# Bubbler.net
KiCad netlist of a schematic drawn in EAGLE
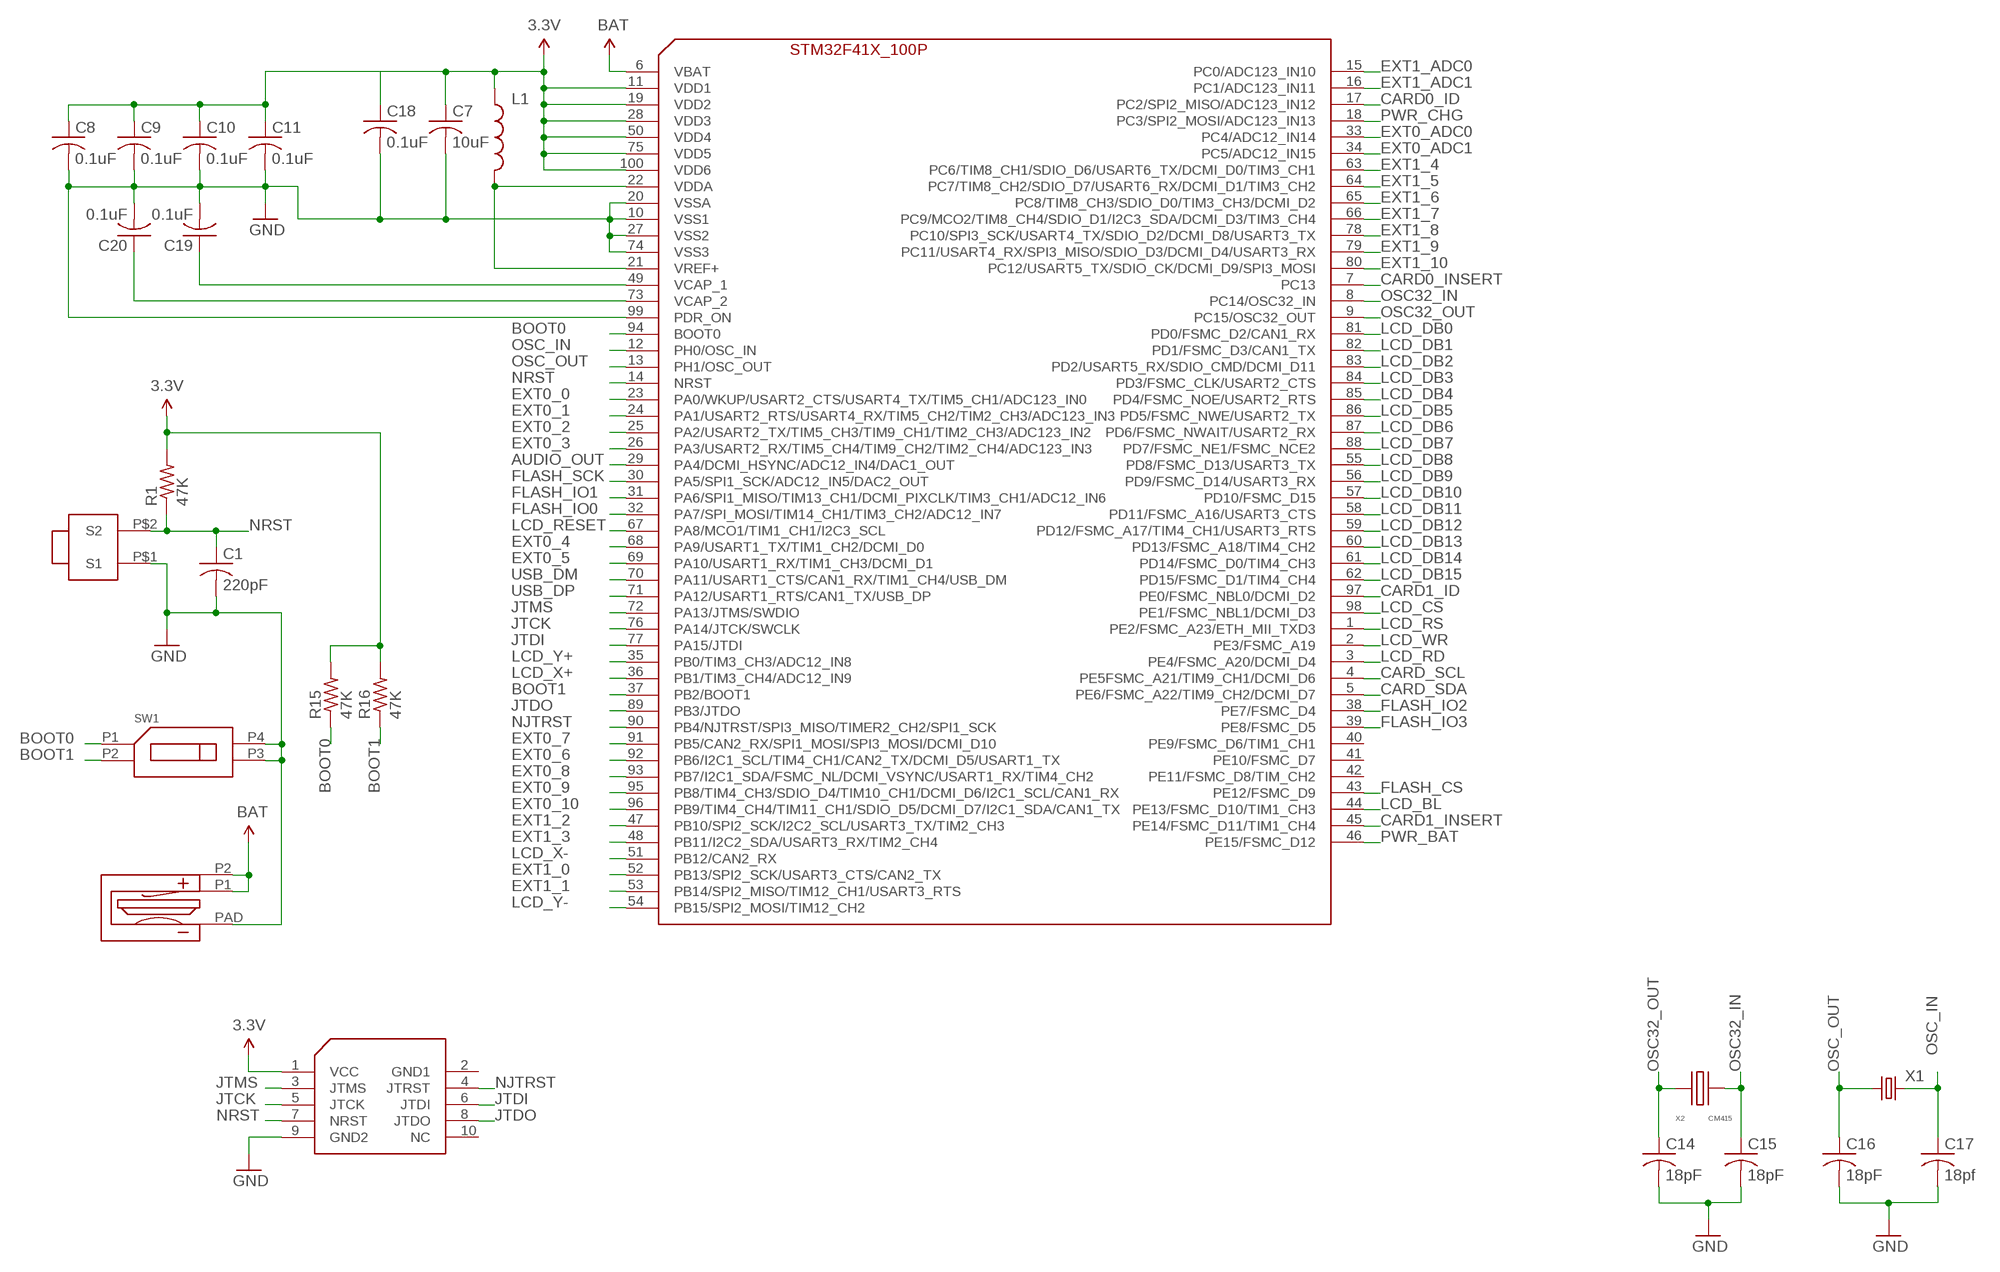
[diagram p0: schematic, sheet 1]
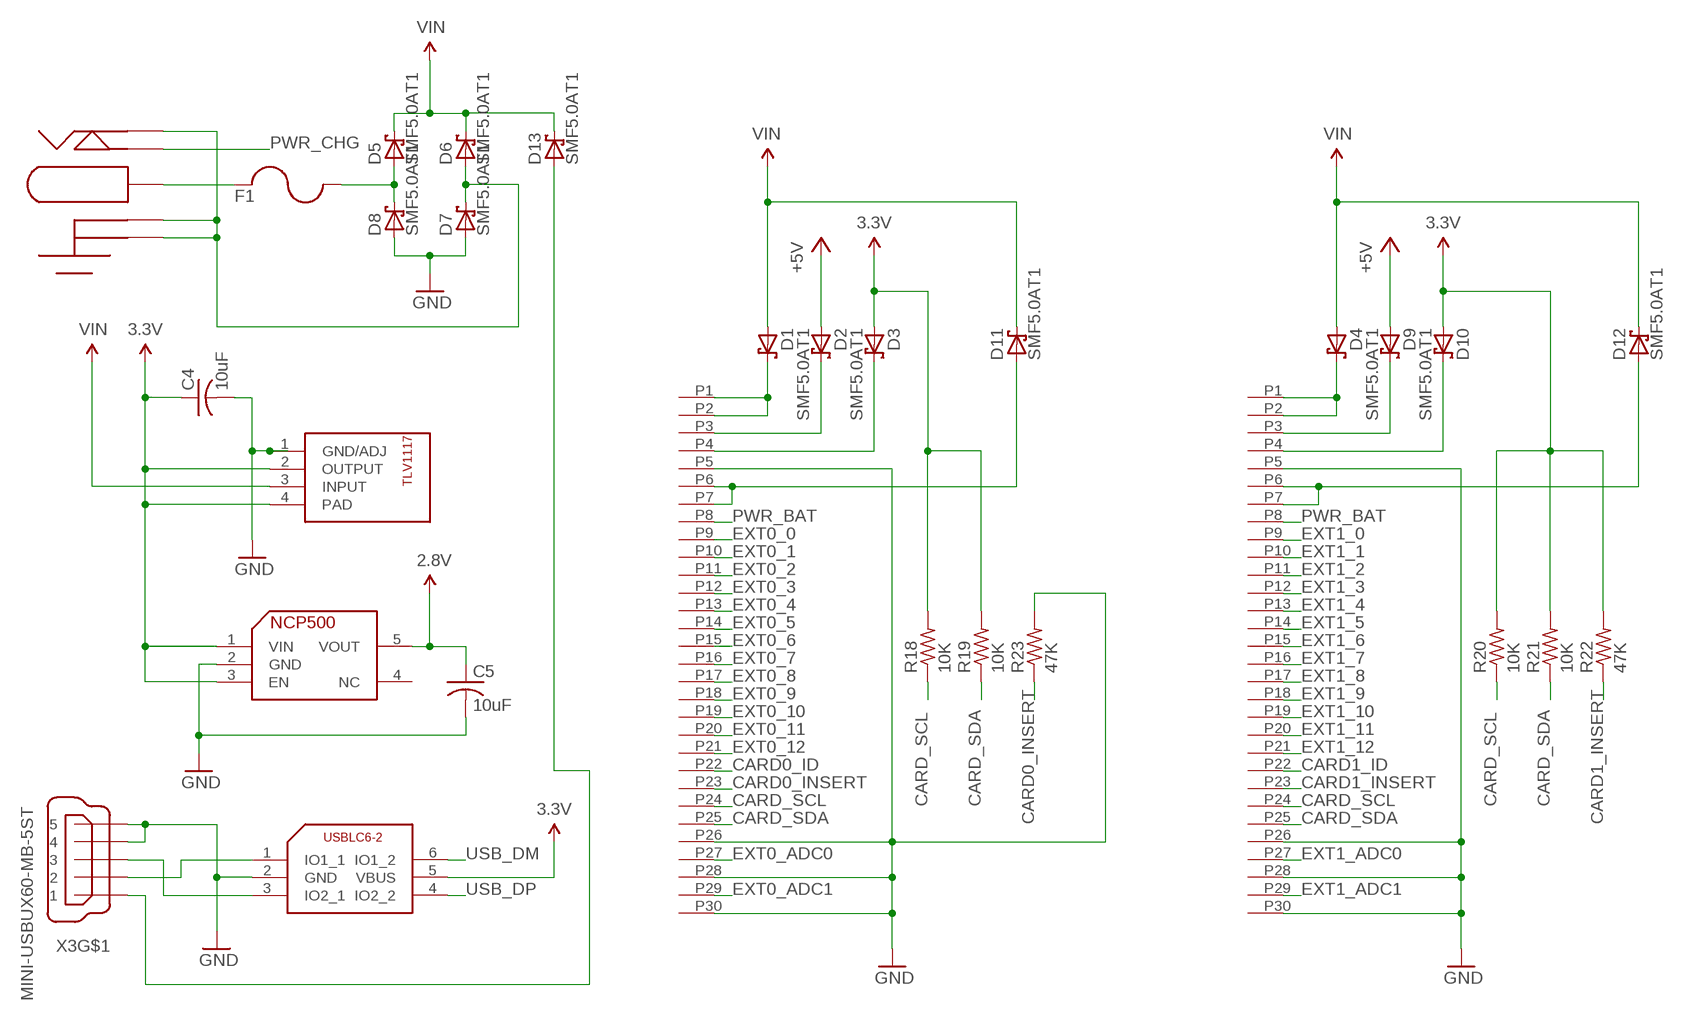
[diagram p1: schematic, sheet 2]
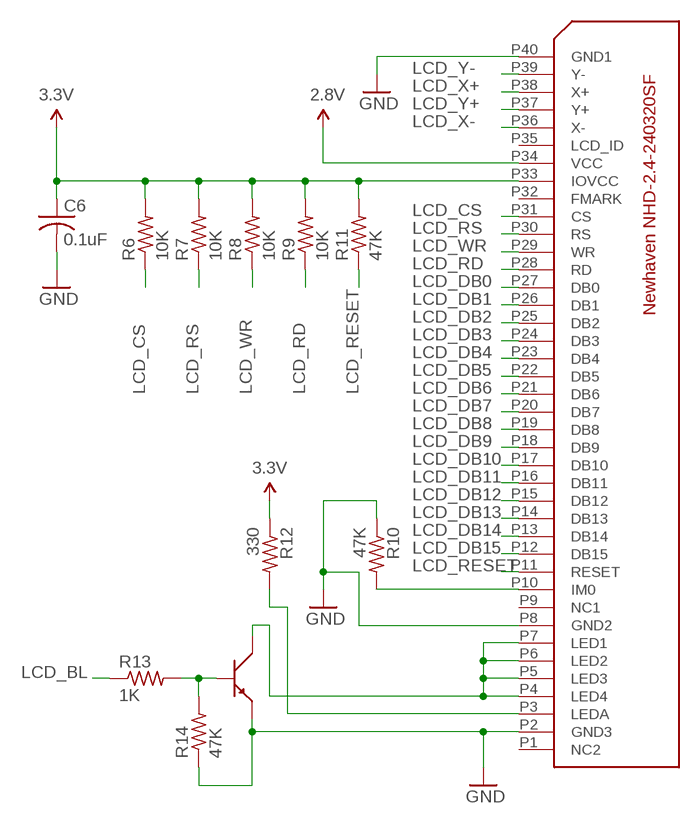
[diagram p2: schematic, sheet 3]
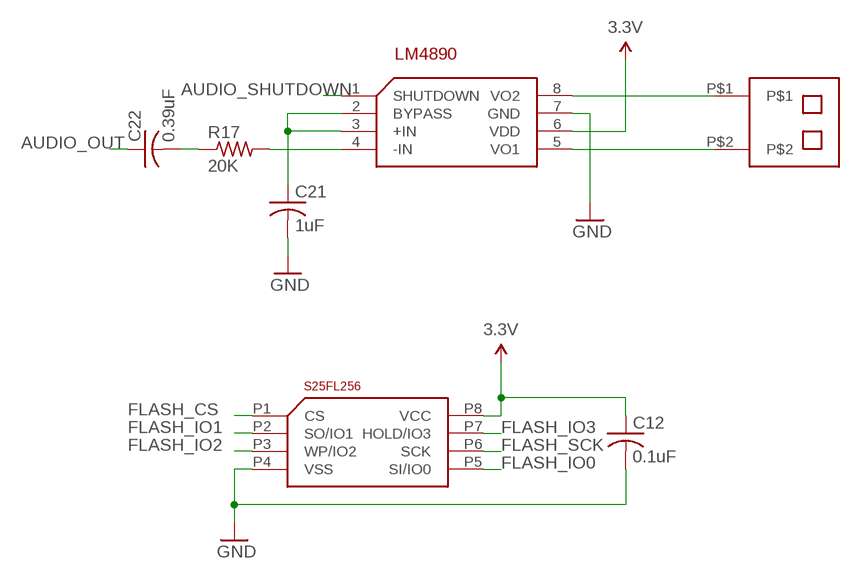
[diagram p3: schematic, sheet 4]

(export (version "E")
  (design (tool "Eeschema 10.0.6"))
  (components
    (comp (ref "B1")
      (value "BATTERY-LINX-HLD-001")
      (footprint "eagle-import:BATTERY-LINX-HLD-001")
      (libsource (lib "eagle-import") (part "BATTERY-LINX-HLD-001"))
    )
    (comp (ref "C1")
      (value "220pF")
      (footprint "eagle-import:C0402")
      (libsource (lib "eagle-import") (part "C-USC0402"))
    )
    (comp (ref "C7")
      (value "10uF")
      (footprint "eagle-import:C0805")
      (libsource (lib "eagle-import") (part "C-USC0805"))
    )
    (comp (ref "C8")
      (value "0.1uF")
      (footprint "eagle-import:C0402")
      (libsource (lib "eagle-import") (part "C-USC0402"))
    )
    (comp (ref "C9")
      (value "0.1uF")
      (footprint "eagle-import:C0402")
      (libsource (lib "eagle-import") (part "C-USC0402"))
    )
    (comp (ref "C10")
      (value "0.1uF")
      (footprint "eagle-import:C0402")
      (libsource (lib "eagle-import") (part "C-USC0402"))
    )
    (comp (ref "C11")
      (value "0.1uF")
      (footprint "eagle-import:C0402")
      (libsource (lib "eagle-import") (part "C-USC0402"))
    )
    (comp (ref "C14")
      (value "18pF")
      (footprint "eagle-import:C0402")
      (libsource (lib "eagle-import") (part "C-USC0402"))
    )
    (comp (ref "C15")
      (value "18pF")
      (footprint "eagle-import:C0402")
      (libsource (lib "eagle-import") (part "C-USC0402"))
    )
    (comp (ref "C16")
      (value "18pF")
      (footprint "eagle-import:C0402")
      (libsource (lib "eagle-import") (part "C-USC0402"))
    )
    (comp (ref "C17")
      (value "18pf")
      (footprint "eagle-import:C0402")
      (libsource (lib "eagle-import") (part "C-USC0402"))
    )
    (comp (ref "C18")
      (value "0.1uF")
      (footprint "eagle-import:C0402")
      (libsource (lib "eagle-import") (part "C-USC0402"))
    )
    (comp (ref "C19")
      (value "0.1uF")
      (footprint "eagle-import:C0402")
      (libsource (lib "eagle-import") (part "C-USC0402"))
    )
    (comp (ref "C20")
      (value "0.1uF")
      (footprint "eagle-import:C0402")
      (libsource (lib "eagle-import") (part "C-USC0402"))
    )
    (comp (ref "L1")
      (value "INDUCTOR0603")
      (footprint "eagle-import:0603")
      (libsource (lib "eagle-import") (part "INDUCTOR0603"))
    )
    (comp (ref "R1")
      (value "47K")
      (footprint "eagle-import:R0402")
      (libsource (lib "eagle-import") (part "R-US_R0402"))
    )
    (comp (ref "R15")
      (value "47K")
      (footprint "eagle-import:R0402")
      (libsource (lib "eagle-import") (part "R-US_R0402"))
    )
    (comp (ref "R16")
      (value "47K")
      (footprint "eagle-import:R0402")
      (libsource (lib "eagle-import") (part "R-US_R0402"))
    )
    (comp (ref "SW1")
      (value "SWITCH-DIP-GDH-02")
      (footprint "eagle-import:SWITCH-DIP-GDH-02")
      (libsource (lib "eagle-import") (part "SWITCH-DIP-GDH-02"))
    )
    (comp (ref "SW2")
      (value "ITT-SWITCH-KSS-G")
      (footprint "eagle-import:ITT-KSS-G")
      (libsource (lib "eagle-import") (part "ITT-SWITCH-KSS-G"))
    )
    (comp (ref "U$1")
      (value "STM32-JTAG-10P")
      (footprint "eagle-import:STM32-JTAG-10P")
      (libsource (lib "eagle-import") (part "STM32-JTAG-10P"))
    )
    (comp (ref "U1")
      (value "STM32F41X-100P")
      (footprint "eagle-import:TQFP100")
      (libsource (lib "eagle-import") (part "STM32F41X-100P"))
    )
    (comp (ref "X1")
      (value "CRYSTAL5X3")
      (footprint "eagle-import:CRYSTAL-SMD-5X3")
      (libsource (lib "eagle-import") (part "CRYSTAL5X3"))
    )
    (comp (ref "X2")
      (value "CM415")
      (footprint "eagle-import:CM415")
      (libsource (lib "eagle-import") (part "CM415"))
    )
    (comp (ref "C12")
      (value "0.1uF")
      (footprint "eagle-import:C0402")
      (libsource (lib "eagle-import") (part "C-USC0402"))
    )
    (comp (ref "C21")
      (value "1uF")
      (footprint "eagle-import:C0402")
      (libsource (lib "eagle-import") (part "C-USC0402"))
    )
    (comp (ref "C22")
      (value "0.39uF")
      (footprint "eagle-import:C0402")
      (libsource (lib "eagle-import") (part "C-USC0402"))
    )
    (comp (ref "R17")
      (value "20K")
      (footprint "eagle-import:R0402")
      (libsource (lib "eagle-import") (part "R-US_R0402"))
    )
    (comp (ref "U2")
      (value "SPANSION-S25FL256")
      (footprint "eagle-import:SPANSION-WSON-8")
      (libsource (lib "eagle-import") (part "SPANSION-S25FL256"))
    )
    (comp (ref "U3")
      (value "LM4890")
      (footprint "eagle-import:TSSOP8")
      (libsource (lib "eagle-import") (part "LM4890"))
    )
    (comp (ref "U7")
      (value "MOLEX-1.25-WTB-RA-CONN-2POS")
      (footprint "eagle-import:MOLEX-1.25WTB-RA-CONN")
      (libsource (lib "eagle-import") (part "MOLEX-1.25-WTB-RA-CONN-2POS"))
    )
    (comp (ref "C4")
      (value "10uF")
      (footprint "eagle-import:C1206")
      (libsource (lib "eagle-import") (part "C-USC1206"))
    )
    (comp (ref "C5")
      (value "10uF")
      (footprint "eagle-import:C1206")
      (libsource (lib "eagle-import") (part "C-USC1206"))
    )
    (comp (ref "CARD0")
      (value "CONNECTOR-JAE-TX24-30F")
      (footprint "eagle-import:CONNECTOR-JAE-TX24-30")
      (libsource (lib "eagle-import") (part "CONNECTOR-JAE-TX24-30F"))
    )
    (comp (ref "CARD1")
      (value "CONNECTOR-JAE-TX24-30F")
      (footprint "eagle-import:CONNECTOR-JAE-TX24-30")
      (libsource (lib "eagle-import") (part "CONNECTOR-JAE-TX24-30F"))
    )
    (comp (ref "D1")
      (value "SCHOTTKY-DIODESMD")
      (footprint "eagle-import:SMB")
      (libsource (lib "eagle-import") (part "SCHOTTKY-DIODESMD"))
    )
    (comp (ref "D2")
      (value "SMF5.0AT1")
      (footprint "eagle-import:SOD123FL")
      (libsource (lib "eagle-import") (part "SMF5.0AT1"))
    )
    (comp (ref "D3")
      (value "SMF5.0AT1")
      (footprint "eagle-import:SOD123FL")
      (libsource (lib "eagle-import") (part "SMF5.0AT1"))
    )
    (comp (ref "D4")
      (value "SCHOTTKY-DIODESMD")
      (footprint "eagle-import:SMB")
      (libsource (lib "eagle-import") (part "SCHOTTKY-DIODESMD"))
    )
    (comp (ref "D5")
      (value "SMF5.0AT1")
      (footprint "eagle-import:SOD123FL")
      (libsource (lib "eagle-import") (part "SMF5.0AT1"))
    )
    (comp (ref "D6")
      (value "SMF5.0AT1")
      (footprint "eagle-import:SOD123FL")
      (libsource (lib "eagle-import") (part "SMF5.0AT1"))
    )
    (comp (ref "D7")
      (value "SMF5.0AT1")
      (footprint "eagle-import:SOD123FL")
      (libsource (lib "eagle-import") (part "SMF5.0AT1"))
    )
    (comp (ref "D8")
      (value "SMF5.0AT1")
      (footprint "eagle-import:SOD123FL")
      (libsource (lib "eagle-import") (part "SMF5.0AT1"))
    )
    (comp (ref "D9")
      (value "SMF5.0AT1")
      (footprint "eagle-import:SOD123FL")
      (libsource (lib "eagle-import") (part "SMF5.0AT1"))
    )
    (comp (ref "D10")
      (value "SMF5.0AT1")
      (footprint "eagle-import:SOD123FL")
      (libsource (lib "eagle-import") (part "SMF5.0AT1"))
    )
    (comp (ref "D11")
      (value "SMF5.0AT1")
      (footprint "eagle-import:SOD123FL")
      (libsource (lib "eagle-import") (part "SMF5.0AT1"))
    )
    (comp (ref "D12")
      (value "SMF5.0AT1")
      (footprint "eagle-import:SOD123FL")
      (libsource (lib "eagle-import") (part "SMF5.0AT1"))
    )
    (comp (ref "D13")
      (value "SMF5.0AT1")
      (footprint "eagle-import:SOD123FL")
      (libsource (lib "eagle-import") (part "SMF5.0AT1"))
    )
    (comp (ref "F1")
      (value "BOURNES-PTC-MF-SMXXXMF-SM030")
      (footprint "eagle-import:MF-SM030")
      (libsource (lib "eagle-import") (part "BOURNES-PTC-MF-SMXXXMF-SM030"))
    )
    (comp (ref "R18")
      (value "10K")
      (footprint "eagle-import:R0402")
      (libsource (lib "eagle-import") (part "R-US_R0402"))
    )
    (comp (ref "R19")
      (value "10K")
      (footprint "eagle-import:R0402")
      (libsource (lib "eagle-import") (part "R-US_R0402"))
    )
    (comp (ref "R20")
      (value "10K")
      (footprint "eagle-import:R0402")
      (libsource (lib "eagle-import") (part "R-US_R0402"))
    )
    (comp (ref "R21")
      (value "10K")
      (footprint "eagle-import:R0402")
      (libsource (lib "eagle-import") (part "R-US_R0402"))
    )
    (comp (ref "R22")
      (value "47K")
      (footprint "eagle-import:R0402")
      (libsource (lib "eagle-import") (part "R-US_R0402"))
    )
    (comp (ref "R23")
      (value "47K")
      (footprint "eagle-import:R0402")
      (libsource (lib "eagle-import") (part "R-US_R0402"))
    )
    (comp (ref "U$2")
      (value "DCJACK-CUI-PJ051AH")
      (footprint "eagle-import:DCJACK_CUI_PJ012B")
      (libsource (lib "eagle-import") (part "DCJACK-CUI-PJ051AH"))
    )
    (comp (ref "U$7")
      (value "NCP500")
      (footprint "eagle-import:SOT23-5L")
      (libsource (lib "eagle-import") (part "NCP500"))
    )
    (comp (ref "U5")
      (value "USBLC6-2")
      (footprint "eagle-import:SOT23-6L")
      (libsource (lib "eagle-import") (part "USBLC6-2"))
    )
    (comp (ref "U6")
      (value "TLV1117")
      (footprint "eagle-import:SOT223")
      (libsource (lib "eagle-import") (part "TLV1117"))
    )
    (comp (ref "X3")
      (value "MINI-USBUX60-MB-5ST")
      (footprint "eagle-import:DUBLIB_UX60-MB-5ST")
      (libsource (lib "eagle-import") (part "MINI-USBUX60-MB-5ST"))
    )
    (comp (ref "C6")
      (value "0.1uF")
      (footprint "eagle-import:C0402")
      (libsource (lib "eagle-import") (part "C-USC0402"))
    )
    (comp (ref "R6")
      (value "10K")
      (footprint "eagle-import:R0402")
      (libsource (lib "eagle-import") (part "R-US_R0402"))
    )
    (comp (ref "R7")
      (value "10K")
      (footprint "eagle-import:R0402")
      (libsource (lib "eagle-import") (part "R-US_R0402"))
    )
    (comp (ref "R8")
      (value "10K")
      (footprint "eagle-import:R0402")
      (libsource (lib "eagle-import") (part "R-US_R0402"))
    )
    (comp (ref "R9")
      (value "10K")
      (footprint "eagle-import:R0402")
      (libsource (lib "eagle-import") (part "R-US_R0402"))
    )
    (comp (ref "R10")
      (value "47K")
      (footprint "eagle-import:R0402")
      (libsource (lib "eagle-import") (part "R-US_R0402"))
    )
    (comp (ref "R11")
      (value "47K")
      (footprint "eagle-import:R0402")
      (libsource (lib "eagle-import") (part "R-US_R0402"))
    )
    (comp (ref "R12")
      (value "330")
      (footprint "eagle-import:R1206")
      (libsource (lib "eagle-import") (part "R-US_R1206"))
    )
    (comp (ref "R13")
      (value "1K")
      (footprint "eagle-import:R0402")
      (libsource (lib "eagle-import") (part "R-US_R0402"))
    )
    (comp (ref "R14")
      (value "47K")
      (footprint "eagle-import:R0402")
      (libsource (lib "eagle-import") (part "R-US_R0402"))
    )
    (comp (ref "U$10")
      (value "NHD-2.4-240320SF")
      (footprint "eagle-import:MOLEX-534132-060")
      (libsource (lib "eagle-import") (part "NHD-2.4-240320SF"))
    )
    (comp (ref "U4")
      (value "BIPOLAR-PMBT6428")
      (footprint "eagle-import:DUBLIB_SOT23")
      (libsource (lib "eagle-import") (part "BIPOLAR-PMBT6428"))
    )
  )
  (nets
    (net (code "1") (name "+5V") (class "Default")
      (node (ref "D2") (pin "A") (pinfunction "A_A") (pintype "passive"))
      (node (ref "D9") (pin "A") (pinfunction "A_A") (pintype "passive"))
    )
    (net (code "2") (name "2.8V") (class "Default")
      (node (ref "C5") (pin "1") (pinfunction "1_1") (pintype "passive"))
      (node (ref "U$10") (pin "P34") (pinfunction "VCC_P34") (pintype "bidirectional"))
      (node (ref "U$7") (pin "5") (pinfunction "VOUT_5") (pintype "bidirectional"))
    )
    (net (code "3") (name "3.3V") (class "Default")
      (node (ref "C10") (pin "1") (pinfunction "1_1") (pintype "passive"))
      (node (ref "C11") (pin "1") (pinfunction "1_1") (pintype "passive"))
      (node (ref "C12") (pin "1") (pinfunction "1_1") (pintype "passive"))
      (node (ref "C18") (pin "1") (pinfunction "1_1") (pintype "passive"))
      (node (ref "C4") (pin "1") (pinfunction "1_1") (pintype "passive"))
      (node (ref "C6") (pin "1") (pinfunction "1_1") (pintype "passive"))
      (node (ref "C7") (pin "1") (pinfunction "1_1") (pintype "passive"))
      (node (ref "C8") (pin "1") (pinfunction "1_1") (pintype "passive"))
      (node (ref "C9") (pin "1") (pinfunction "1_1") (pintype "passive"))
      (node (ref "D10") (pin "A") (pinfunction "A_A") (pintype "passive"))
      (node (ref "D3") (pin "A") (pinfunction "A_A") (pintype "passive"))
      (node (ref "L1") (pin "1") (pinfunction "1_1") (pintype "passive"))
      (node (ref "R1") (pin "2") (pinfunction "2_2") (pintype "passive"))
      (node (ref "R11") (pin "2") (pinfunction "2_2") (pintype "passive"))
      (node (ref "R12") (pin "1") (pinfunction "1_1") (pintype "passive"))
      (node (ref "R15") (pin "2") (pinfunction "2_2") (pintype "passive"))
      (node (ref "R16") (pin "2") (pinfunction "2_2") (pintype "passive"))
      (node (ref "R18") (pin "2") (pinfunction "2_2") (pintype "passive"))
      (node (ref "R19") (pin "2") (pinfunction "2_2") (pintype "passive"))
      (node (ref "R20") (pin "2") (pinfunction "2_2") (pintype "passive"))
      (node (ref "R21") (pin "2") (pinfunction "2_2") (pintype "passive"))
      (node (ref "R22") (pin "2") (pinfunction "2_2") (pintype "passive"))
      (node (ref "R6") (pin "2") (pinfunction "2_2") (pintype "passive"))
      (node (ref "R7") (pin "2") (pinfunction "2_2") (pintype "passive"))
      (node (ref "R8") (pin "2") (pinfunction "2_2") (pintype "passive"))
      (node (ref "R9") (pin "2") (pinfunction "2_2") (pintype "passive"))
      (node (ref "U$1") (pin "1") (pinfunction "VCC_1") (pintype "bidirectional"))
      (node (ref "U$10") (pin "P33") (pinfunction "IOVCC_P33") (pintype "bidirectional"))
      (node (ref "U$7") (pin "1") (pinfunction "VIN_1") (pintype "bidirectional"))
      (node (ref "U$7") (pin "3") (pinfunction "EN_3") (pintype "bidirectional"))
      (node (ref "U1") (pin "100") (pinfunction "VDD6_100") (pintype "bidirectional"))
      (node (ref "U1") (pin "11") (pinfunction "VDD1_11") (pintype "bidirectional"))
      (node (ref "U1") (pin "19") (pinfunction "VDD2_19") (pintype "bidirectional"))
      (node (ref "U1") (pin "28") (pinfunction "VDD3_28") (pintype "bidirectional"))
      (node (ref "U1") (pin "50") (pinfunction "VDD4_50") (pintype "bidirectional"))
      (node (ref "U1") (pin "75") (pinfunction "VDD5_75") (pintype "bidirectional"))
      (node (ref "U2") (pin "P8") (pinfunction "VCC_P8") (pintype "bidirectional"))
      (node (ref "U3") (pin "6") (pinfunction "VDD_6") (pintype "bidirectional"))
      (node (ref "U5") (pin "5") (pinfunction "VBUS_5") (pintype "bidirectional"))
      (node (ref "U6") (pin "2") (pinfunction "OUTPUT_2") (pintype "bidirectional"))
      (node (ref "U6") (pin "4") (pinfunction "PAD_4") (pintype "bidirectional"))
    )
    (net (code "4") (name "AUDIO_OUT") (class "Default")
      (node (ref "C22") (pin "1") (pinfunction "1_1") (pintype "passive"))
      (node (ref "U1") (pin "29") (pinfunction "PA4/DCMI_HSYNC/ADC12_IN4/DAC1_OUT_29") (pintype "bidirectional"))
    )
    (net (code "5") (name "AUDIO_SHUTDOWN") (class "Default")
      (node (ref "U3") (pin "1") (pinfunction "SHUTDOWN_1") (pintype "bidirectional"))
    )
    (net (code "6") (name "BAT") (class "Default")
      (node (ref "B1") (pin "P1") (pinfunction "BAT1_P1") (pintype "power_in"))
      (node (ref "B1") (pin "P2") (pinfunction "BAT2_P2") (pintype "power_in"))
      (node (ref "U1") (pin "6") (pinfunction "VBAT_6") (pintype "bidirectional"))
    )
    (net (code "7") (name "BOOT0") (class "Default")
      (node (ref "R15") (pin "1") (pinfunction "1_1") (pintype "passive"))
      (node (ref "SW1") (pin "P1") (pinfunction "SW0_0_P1") (pintype "bidirectional"))
      (node (ref "U1") (pin "94") (pinfunction "BOOT0_94") (pintype "bidirectional"))
    )
    (net (code "8") (name "BOOT1") (class "Default")
      (node (ref "R16") (pin "1") (pinfunction "1_1") (pintype "passive"))
      (node (ref "SW1") (pin "P2") (pinfunction "SW1_0_P2") (pintype "bidirectional"))
      (node (ref "U1") (pin "37") (pinfunction "PB2/BOOT1_37") (pintype "bidirectional"))
    )
    (net (code "9") (name "CARD0_ID") (class "Default")
      (node (ref "CARD0") (pin "P22") (pinfunction "P22_P22") (pintype "bidirectional"))
      (node (ref "U1") (pin "17") (pinfunction "PC2/SPI2_MISO/ADC123_IN12_17") (pintype "bidirectional"))
    )
    (net (code "10") (name "CARD0_INSERT") (class "Default")
      (node (ref "CARD0") (pin "P23") (pinfunction "P23_P23") (pintype "bidirectional"))
      (node (ref "R23") (pin "1") (pinfunction "1_1") (pintype "passive"))
      (node (ref "U1") (pin "7") (pinfunction "PC13_7") (pintype "bidirectional"))
    )
    (net (code "11") (name "CARD1_ID") (class "Default")
      (node (ref "CARD1") (pin "P22") (pinfunction "P22_P22") (pintype "bidirectional"))
      (node (ref "U1") (pin "97") (pinfunction "PE0/FSMC_NBL0/DCMI_D2_97") (pintype "bidirectional"))
    )
    (net (code "12") (name "CARD1_INSERT") (class "Default")
      (node (ref "CARD1") (pin "P23") (pinfunction "P23_P23") (pintype "bidirectional"))
      (node (ref "R22") (pin "1") (pinfunction "1_1") (pintype "passive"))
      (node (ref "U1") (pin "45") (pinfunction "PE14/FSMC_D11/TIM1_CH4_45") (pintype "bidirectional"))
    )
    (net (code "13") (name "CARD_SCL") (class "Default")
      (node (ref "CARD0") (pin "P24") (pinfunction "P24_P24") (pintype "bidirectional"))
      (node (ref "CARD1") (pin "P24") (pinfunction "P24_P24") (pintype "bidirectional"))
      (node (ref "R18") (pin "1") (pinfunction "1_1") (pintype "passive"))
      (node (ref "R20") (pin "1") (pinfunction "1_1") (pintype "passive"))
      (node (ref "U1") (pin "4") (pinfunction "PE5FSMC_A21/TIM9_CH1/DCMI_D6_4") (pintype "bidirectional"))
    )
    (net (code "14") (name "CARD_SDA") (class "Default")
      (node (ref "CARD0") (pin "P25") (pinfunction "P25_P25") (pintype "bidirectional"))
      (node (ref "CARD1") (pin "P25") (pinfunction "P25_P25") (pintype "bidirectional"))
      (node (ref "R19") (pin "1") (pinfunction "1_1") (pintype "passive"))
      (node (ref "R21") (pin "1") (pinfunction "1_1") (pintype "passive"))
      (node (ref "U1") (pin "5") (pinfunction "PE6/FSMC_A22/TIM9_CH2/DCMI_D7_5") (pintype "bidirectional"))
    )
    (net (code "15") (name "EXT0_0") (class "Default")
      (node (ref "CARD0") (pin "P9") (pinfunction "P9_P9") (pintype "bidirectional"))
      (node (ref "U1") (pin "23") (pinfunction "PA0/WKUP/USART2_CTS/USART4_TX/TIM5_CH1/ADC123_IN0_23") (pintype "bidirectional"))
    )
    (net (code "16") (name "EXT0_1") (class "Default")
      (node (ref "CARD0") (pin "P10") (pinfunction "P10_P10") (pintype "bidirectional"))
      (node (ref "U1") (pin "24") (pinfunction "PA1/USART2_RTS/USART4_RX/TIM5_CH2/TIM2_CH3/ADC123_IN3_24") (pintype "bidirectional"))
    )
    (net (code "17") (name "EXT0_2") (class "Default")
      (node (ref "CARD0") (pin "P11") (pinfunction "P11_P11") (pintype "bidirectional"))
      (node (ref "U1") (pin "25") (pinfunction "PA2/USART2_TX/TIM5_CH3/TIM9_CH1/TIM2_CH3/ADC123_IN2_25") (pintype "bidirectional"))
    )
    (net (code "18") (name "EXT0_3") (class "Default")
      (node (ref "CARD0") (pin "P12") (pinfunction "P12_P12") (pintype "bidirectional"))
      (node (ref "U1") (pin "26") (pinfunction "PA3/USART2_RX/TIM5_CH4/TIM9_CH2/TIM2_CH4/ADC123_IN3_26") (pintype "bidirectional"))
    )
    (net (code "19") (name "EXT0_4") (class "Default")
      (node (ref "CARD0") (pin "P13") (pinfunction "P13_P13") (pintype "bidirectional"))
      (node (ref "U1") (pin "68") (pinfunction "PA9/USART1_TX/TIM1_CH2/DCMI_D0_68") (pintype "bidirectional"))
    )
    (net (code "20") (name "EXT0_5") (class "Default")
      (node (ref "CARD0") (pin "P14") (pinfunction "P14_P14") (pintype "bidirectional"))
      (node (ref "U1") (pin "69") (pinfunction "PA10/USART1_RX/TIM1_CH3/DCMI_D1_69") (pintype "bidirectional"))
    )
    (net (code "21") (name "EXT0_6") (class "Default")
      (node (ref "CARD0") (pin "P15") (pinfunction "P15_P15") (pintype "bidirectional"))
      (node (ref "U1") (pin "92") (pinfunction "PB6/I2C1_SCL/TIM4_CH1/CAN2_TX/DCMI_D5/USART1_TX_92") (pintype "bidirectional"))
    )
    (net (code "22") (name "EXT0_7") (class "Default")
      (node (ref "CARD0") (pin "P16") (pinfunction "P16_P16") (pintype "bidirectional"))
      (node (ref "U1") (pin "91") (pinfunction "PB5/CAN2_RX/SPI1_MOSI/SPI3_MOSI/DCMI_D10_91") (pintype "bidirectional"))
    )
    (net (code "23") (name "EXT0_8") (class "Default")
      (node (ref "CARD0") (pin "P17") (pinfunction "P17_P17") (pintype "bidirectional"))
      (node (ref "U1") (pin "93") (pinfunction "PB7/I2C1_SDA/FSMC_NL/DCMI_VSYNC/USART1_RX/TIM4_CH2_93") (pintype "bidirectional"))
    )
    (net (code "24") (name "EXT0_9") (class "Default")
      (node (ref "CARD0") (pin "P18") (pinfunction "P18_P18") (pintype "bidirectional"))
      (node (ref "U1") (pin "95") (pinfunction "PB8/TIM4_CH3/SDIO_D4/TIM10_CH1/DCMI_D6/I2C1_SCL/CAN1_RX_95") (pintype "bidirectional"))
    )
    (net (code "25") (name "EXT0_10") (class "Default")
      (node (ref "CARD0") (pin "P19") (pinfunction "P19_P19") (pintype "bidirectional"))
      (node (ref "U1") (pin "96") (pinfunction "PB9/TIM4_CH4/TIM11_CH1/SDIO_D5/DCMI_D7/I2C1_SDA/CAN1_TX_96") (pintype "bidirectional"))
    )
    (net (code "26") (name "EXT0_11") (class "Default")
      (node (ref "CARD0") (pin "P20") (pinfunction "P20_P20") (pintype "bidirectional"))
    )
    (net (code "27") (name "EXT0_12") (class "Default")
      (node (ref "CARD0") (pin "P21") (pinfunction "P21_P21") (pintype "bidirectional"))
    )
    (net (code "28") (name "EXT0_ADC0") (class "Default")
      (node (ref "CARD0") (pin "P27") (pinfunction "P27_P27") (pintype "bidirectional"))
      (node (ref "U1") (pin "33") (pinfunction "PC4/ADC12_IN14_33") (pintype "bidirectional"))
    )
    (net (code "29") (name "EXT0_ADC1") (class "Default")
      (node (ref "CARD0") (pin "P29") (pinfunction "P29_P29") (pintype "bidirectional"))
      (node (ref "U1") (pin "34") (pinfunction "PC5/ADC12_IN15_34") (pintype "bidirectional"))
    )
    (net (code "30") (name "EXT1_0") (class "Default")
      (node (ref "CARD1") (pin "P9") (pinfunction "P9_P9") (pintype "bidirectional"))
      (node (ref "U1") (pin "52") (pinfunction "PB13/SPI2_SCK/USART3_CTS/CAN2_TX_52") (pintype "bidirectional"))
    )
    (net (code "31") (name "EXT1_1") (class "Default")
      (node (ref "CARD1") (pin "P10") (pinfunction "P10_P10") (pintype "bidirectional"))
      (node (ref "U1") (pin "53") (pinfunction "PB14/SPI2_MISO/TIM12_CH1/USART3_RTS_53") (pintype "bidirectional"))
    )
    (net (code "32") (name "EXT1_2") (class "Default")
      (node (ref "CARD1") (pin "P11") (pinfunction "P11_P11") (pintype "bidirectional"))
      (node (ref "U1") (pin "47") (pinfunction "PB10/SPI2_SCK/I2C2_SCL/USART3_TX/TIM2_CH3_47") (pintype "bidirectional"))
    )
    (net (code "33") (name "EXT1_3") (class "Default")
      (node (ref "CARD1") (pin "P12") (pinfunction "P12_P12") (pintype "bidirectional"))
      (node (ref "U1") (pin "48") (pinfunction "PB11/I2C2_SDA/USART3_RX/TIM2_CH4_48") (pintype "bidirectional"))
    )
    (net (code "34") (name "EXT1_4") (class "Default")
      (node (ref "CARD1") (pin "P13") (pinfunction "P13_P13") (pintype "bidirectional"))
      (node (ref "U1") (pin "63") (pinfunction "PC6/TIM8_CH1/SDIO_D6/USART6_TX/DCMI_D0/TIM3_CH1_63") (pintype "bidirectional"))
    )
    (net (code "35") (name "EXT1_5") (class "Default")
      (node (ref "CARD1") (pin "P14") (pinfunction "P14_P14") (pintype "bidirectional"))
      (node (ref "U1") (pin "64") (pinfunction "PC7/TIM8_CH2/SDIO_D7/USART6_RX/DCMI_D1/TIM3_CH2_64") (pintype "bidirectional"))
    )
    (net (code "36") (name "EXT1_6") (class "Default")
      (node (ref "CARD1") (pin "P15") (pinfunction "P15_P15") (pintype "bidirectional"))
      (node (ref "U1") (pin "65") (pinfunction "PC8/TIM8_CH3/SDIO_D0/TIM3_CH3/DCMI_D2_65") (pintype "bidirectional"))
    )
    (net (code "37") (name "EXT1_7") (class "Default")
      (node (ref "CARD1") (pin "P16") (pinfunction "P16_P16") (pintype "bidirectional"))
      (node (ref "U1") (pin "66") (pinfunction "PC9/MCO2/TIM8_CH4/SDIO_D1/I2C3_SDA/DCMI_D3/TIM3_CH4_66") (pintype "bidirectional"))
    )
    (net (code "38") (name "EXT1_8") (class "Default")
      (node (ref "CARD1") (pin "P17") (pinfunction "P17_P17") (pintype "bidirectional"))
      (node (ref "U1") (pin "78") (pinfunction "PC10/SPI3_SCK/USART4_TX/SDIO_D2/DCMI_D8/USART3_TX_78") (pintype "bidirectional"))
    )
    (net (code "39") (name "EXT1_9") (class "Default")
      (node (ref "CARD1") (pin "P18") (pinfunction "P18_P18") (pintype "bidirectional"))
      (node (ref "U1") (pin "79") (pinfunction "PC11/USART4_RX/SPI3_MISO/SDIO_D3/DCMI_D4/USART3_RX_79") (pintype "bidirectional"))
    )
    (net (code "40") (name "EXT1_10") (class "Default")
      (node (ref "CARD1") (pin "P19") (pinfunction "P19_P19") (pintype "bidirectional"))
      (node (ref "U1") (pin "80") (pinfunction "PC12/USART5_TX/SDIO_CK/DCMI_D9/SPI3_MOSI_80") (pintype "bidirectional"))
    )
    (net (code "41") (name "EXT1_11") (class "Default")
      (node (ref "CARD1") (pin "P20") (pinfunction "P20_P20") (pintype "bidirectional"))
    )
    (net (code "42") (name "EXT1_12") (class "Default")
      (node (ref "CARD1") (pin "P21") (pinfunction "P21_P21") (pintype "bidirectional"))
    )
    (net (code "43") (name "EXT1_ADC0") (class "Default")
      (node (ref "CARD1") (pin "P27") (pinfunction "P27_P27") (pintype "bidirectional"))
      (node (ref "U1") (pin "15") (pinfunction "PC0/ADC123_IN10_15") (pintype "bidirectional"))
    )
    (net (code "44") (name "EXT1_ADC1") (class "Default")
      (node (ref "CARD1") (pin "P29") (pinfunction "P29_P29") (pintype "bidirectional"))
      (node (ref "U1") (pin "16") (pinfunction "PC1/ADC123_IN11_16") (pintype "bidirectional"))
    )
    (net (code "45") (name "FLASH_CS") (class "Default")
      (node (ref "U1") (pin "43") (pinfunction "PE12/FSMC_D9_43") (pintype "bidirectional"))
      (node (ref "U2") (pin "P1") (pinfunction "CS_P1") (pintype "bidirectional"))
    )
    (net (code "46") (name "FLASH_IO0") (class "Default")
      (node (ref "U1") (pin "32") (pinfunction "PA7/SPI_MOSI/TIM14_CH1/TIM3_CH2/ADC12_IN7_32") (pintype "bidirectional"))
      (node (ref "U2") (pin "P5") (pinfunction "SI/IO0_P5") (pintype "bidirectional"))
    )
    (net (code "47") (name "FLASH_IO1") (class "Default")
      (node (ref "U1") (pin "31") (pinfunction "PA6/SPI1_MISO/TIM13_CH1/DCMI_PIXCLK/TIM3_CH1/ADC12_IN6_31") (pintype "bidirectional"))
      (node (ref "U2") (pin "P2") (pinfunction "SO/IO1_P2") (pintype "bidirectional"))
    )
    (net (code "48") (name "FLASH_IO2") (class "Default")
      (node (ref "U1") (pin "38") (pinfunction "PE7/FSMC_D4_38") (pintype "bidirectional"))
      (node (ref "U2") (pin "P3") (pinfunction "WP/IO2_P3") (pintype "bidirectional"))
    )
    (net (code "49") (name "FLASH_IO3") (class "Default")
      (node (ref "U1") (pin "39") (pinfunction "PE8/FSMC_D5_39") (pintype "bidirectional"))
      (node (ref "U2") (pin "P7") (pinfunction "HOLD/IO3_P7") (pintype "bidirectional"))
    )
    (net (code "50") (name "FLASH_SCK") (class "Default")
      (node (ref "U1") (pin "30") (pinfunction "PA5/SPI1_SCK/ADC12_IN5/DAC2_OUT_30") (pintype "bidirectional"))
      (node (ref "U2") (pin "P6") (pinfunction "SCK_P6") (pintype "bidirectional"))
    )
    (net (code "51") (name "GND") (class "Default")
      (node (ref "B1") (pin "PAD") (pinfunction "GND_PAD") (pintype "power_in"))
      (node (ref "C1") (pin "2") (pinfunction "2_2") (pintype "passive"))
      (node (ref "C10") (pin "2") (pinfunction "2_2") (pintype "passive"))
      (node (ref "C11") (pin "2") (pinfunction "2_2") (pintype "passive"))
      (node (ref "C12") (pin "2") (pinfunction "2_2") (pintype "passive"))
      (node (ref "C14") (pin "2") (pinfunction "2_2") (pintype "passive"))
      (node (ref "C15") (pin "2") (pinfunction "2_2") (pintype "passive"))
      (node (ref "C16") (pin "2") (pinfunction "2_2") (pintype "passive"))
      (node (ref "C17") (pin "2") (pinfunction "2_2") (pintype "passive"))
      (node (ref "C18") (pin "2") (pinfunction "2_2") (pintype "passive"))
      (node (ref "C19") (pin "2") (pinfunction "2_2") (pintype "passive"))
      (node (ref "C20") (pin "2") (pinfunction "2_2") (pintype "passive"))
      (node (ref "C21") (pin "2") (pinfunction "2_2") (pintype "passive"))
      (node (ref "C4") (pin "2") (pinfunction "2_2") (pintype "passive"))
      (node (ref "C5") (pin "2") (pinfunction "2_2") (pintype "passive"))
      (node (ref "C6") (pin "2") (pinfunction "2_2") (pintype "passive"))
      (node (ref "C7") (pin "2") (pinfunction "2_2") (pintype "passive"))
      (node (ref "C8") (pin "2") (pinfunction "2_2") (pintype "passive"))
      (node (ref "C9") (pin "2") (pinfunction "2_2") (pintype "passive"))
      (node (ref "CARD0") (pin "P26") (pinfunction "P26_P26") (pintype "bidirectional"))
      (node (ref "CARD0") (pin "P28") (pinfunction "P28_P28") (pintype "bidirectional"))
      (node (ref "CARD0") (pin "P30") (pinfunction "P30_P30") (pintype "bidirectional"))
      (node (ref "CARD0") (pin "P5") (pinfunction "P5_P5") (pintype "bidirectional"))
      (node (ref "CARD1") (pin "P26") (pinfunction "P26_P26") (pintype "bidirectional"))
      (node (ref "CARD1") (pin "P28") (pinfunction "P28_P28") (pintype "bidirectional"))
      (node (ref "CARD1") (pin "P30") (pinfunction "P30_P30") (pintype "bidirectional"))
      (node (ref "CARD1") (pin "P5") (pinfunction "P5_P5") (pintype "bidirectional"))
      (node (ref "D7") (pin "A") (pinfunction "A_A") (pintype "passive"))
      (node (ref "D8") (pin "A") (pinfunction "A_A") (pintype "passive"))
      (node (ref "R10") (pin "1") (pinfunction "1_1") (pintype "passive"))
      (node (ref "R14") (pin "1") (pinfunction "1_1") (pintype "passive"))
      (node (ref "R23") (pin "2") (pinfunction "2_2") (pintype "passive"))
      (node (ref "SW1") (pin "P3") (pinfunction "SW1_1_P3") (pintype "bidirectional"))
      (node (ref "SW1") (pin "P4") (pinfunction "SW0_1_P4") (pintype "bidirectional"))
      (node (ref "SW2") (pin "P$1") (pinfunction "S1_P$1") (pintype "bidirectional"))
      (node (ref "U$1") (pin "9") (pinfunction "GND2_9") (pintype "bidirectional"))
      (node (ref "U$10") (pin "P2") (pinfunction "GND3_P2") (pintype "bidirectional"))
      (node (ref "U$10") (pin "P40") (pinfunction "GND1_P40") (pintype "bidirectional"))
      (node (ref "U$10") (pin "P8") (pinfunction "GND2_P8") (pintype "bidirectional"))
      (node (ref "U$7") (pin "2") (pinfunction "GND_2") (pintype "bidirectional"))
      (node (ref "U1") (pin "10") (pinfunction "VSS1_10") (pintype "bidirectional"))
      (node (ref "U1") (pin "20") (pinfunction "VSSA_20") (pintype "bidirectional"))
      (node (ref "U1") (pin "27") (pinfunction "VSS2_27") (pintype "bidirectional"))
      (node (ref "U1") (pin "74") (pinfunction "VSS3_74") (pintype "bidirectional"))
      (node (ref "U1") (pin "99") (pinfunction "PDR_ON_99") (pintype "bidirectional"))
      (node (ref "U2") (pin "P4") (pinfunction "VSS_P4") (pintype "bidirectional"))
      (node (ref "U3") (pin "7") (pinfunction "GND_7") (pintype "bidirectional"))
      (node (ref "U4") (pin "2") (pinfunction "2_2") (pintype "bidirectional"))
      (node (ref "U5") (pin "2") (pinfunction "GND_2") (pintype "bidirectional"))
      (node (ref "U6") (pin "1") (pinfunction "GND/ADJ_1") (pintype "bidirectional"))
      (node (ref "X3") (pin "4") (pinfunction "4_4") (pintype "input"))
      (node (ref "X3") (pin "5") (pinfunction "5_5") (pintype "input"))
    )
    (net (code "52") (name "JTCK") (class "Default")
      (node (ref "U$1") (pin "5") (pinfunction "JTCK_5") (pintype "bidirectional"))
      (node (ref "U1") (pin "76") (pinfunction "PA14/JTCK/SWCLK_76") (pintype "bidirectional"))
    )
    (net (code "53") (name "JTDI") (class "Default")
      (node (ref "U$1") (pin "6") (pinfunction "JTDI_6") (pintype "bidirectional"))
      (node (ref "U1") (pin "77") (pinfunction "PA15/JTDI_77") (pintype "bidirectional"))
    )
    (net (code "54") (name "JTDO") (class "Default")
      (node (ref "U$1") (pin "8") (pinfunction "JTDO_8") (pintype "bidirectional"))
      (node (ref "U1") (pin "89") (pinfunction "PB3/JTDO_89") (pintype "bidirectional"))
    )
    (net (code "55") (name "JTMS") (class "Default")
      (node (ref "U$1") (pin "3") (pinfunction "JTMS_3") (pintype "bidirectional"))
      (node (ref "U1") (pin "72") (pinfunction "PA13/JTMS/SWDIO_72") (pintype "bidirectional"))
    )
    (net (code "56") (name "LCD_BL") (class "Default")
      (node (ref "R13") (pin "1") (pinfunction "1_1") (pintype "passive"))
      (node (ref "U1") (pin "44") (pinfunction "PE13/FSMC_D10/TIM1_CH3_44") (pintype "bidirectional"))
    )
    (net (code "57") (name "LCD_CS") (class "Default")
      (node (ref "R6") (pin "1") (pinfunction "1_1") (pintype "passive"))
      (node (ref "U$10") (pin "P31") (pinfunction "CS_P31") (pintype "bidirectional"))
      (node (ref "U1") (pin "98") (pinfunction "PE1/FSMC_NBL1/DCMI_D3_98") (pintype "bidirectional"))
    )
    (net (code "58") (name "LCD_DB0") (class "Default")
      (node (ref "U$10") (pin "P27") (pinfunction "DB0_P27") (pintype "bidirectional"))
      (node (ref "U1") (pin "81") (pinfunction "PD0/FSMC_D2/CAN1_RX_81") (pintype "bidirectional"))
    )
    (net (code "59") (name "LCD_DB1") (class "Default")
      (node (ref "U$10") (pin "P26") (pinfunction "DB1_P26") (pintype "bidirectional"))
      (node (ref "U1") (pin "82") (pinfunction "PD1/FSMC_D3/CAN1_TX_82") (pintype "bidirectional"))
    )
    (net (code "60") (name "LCD_DB2") (class "Default")
      (node (ref "U$10") (pin "P25") (pinfunction "DB2_P25") (pintype "bidirectional"))
      (node (ref "U1") (pin "83") (pinfunction "PD2/USART5_RX/SDIO_CMD/DCMI_D11_83") (pintype "bidirectional"))
    )
    (net (code "61") (name "LCD_DB3") (class "Default")
      (node (ref "U$10") (pin "P24") (pinfunction "DB3_P24") (pintype "bidirectional"))
      (node (ref "U1") (pin "84") (pinfunction "PD3/FSMC_CLK/USART2_CTS_84") (pintype "bidirectional"))
    )
    (net (code "62") (name "LCD_DB4") (class "Default")
      (node (ref "U$10") (pin "P23") (pinfunction "DB4_P23") (pintype "bidirectional"))
      (node (ref "U1") (pin "85") (pinfunction "PD4/FSMC_NOE/USART2_RTS_85") (pintype "bidirectional"))
    )
    (net (code "63") (name "LCD_DB5") (class "Default")
      (node (ref "U$10") (pin "P22") (pinfunction "DB5_P22") (pintype "bidirectional"))
      (node (ref "U1") (pin "86") (pinfunction "PD5/FSMC_NWE/USART2_TX_86") (pintype "bidirectional"))
    )
    (net (code "64") (name "LCD_DB6") (class "Default")
      (node (ref "U$10") (pin "P21") (pinfunction "DB6_P21") (pintype "bidirectional"))
      (node (ref "U1") (pin "87") (pinfunction "PD6/FSMC_NWAIT/USART2_RX_87") (pintype "bidirectional"))
    )
    (net (code "65") (name "LCD_DB7") (class "Default")
      (node (ref "U$10") (pin "P20") (pinfunction "DB7_P20") (pintype "bidirectional"))
      (node (ref "U1") (pin "88") (pinfunction "PD7/FSMC_NE1/FSMC_NCE2_88") (pintype "bidirectional"))
    )
    (net (code "66") (name "LCD_DB8") (class "Default")
      (node (ref "U$10") (pin "P19") (pinfunction "DB8_P19") (pintype "bidirectional"))
      (node (ref "U1") (pin "55") (pinfunction "PD8/FSMC_D13/USART3_TX_55") (pintype "bidirectional"))
    )
    (net (code "67") (name "LCD_DB9") (class "Default")
      (node (ref "U$10") (pin "P18") (pinfunction "DB9_P18") (pintype "bidirectional"))
      (node (ref "U1") (pin "56") (pinfunction "PD9/FSMC_D14/USART3_RX_56") (pintype "bidirectional"))
    )
    (net (code "68") (name "LCD_DB10") (class "Default")
      (node (ref "U$10") (pin "P17") (pinfunction "DB10_P17") (pintype "bidirectional"))
      (node (ref "U1") (pin "57") (pinfunction "PD10/FSMC_D15_57") (pintype "bidirectional"))
    )
    (net (code "69") (name "LCD_DB11") (class "Default")
      (node (ref "U$10") (pin "P16") (pinfunction "DB11_P16") (pintype "bidirectional"))
      (node (ref "U1") (pin "58") (pinfunction "PD11/FSMC_A16/USART3_CTS_58") (pintype "bidirectional"))
    )
    (net (code "70") (name "LCD_DB12") (class "Default")
      (node (ref "U$10") (pin "P15") (pinfunction "DB12_P15") (pintype "bidirectional"))
      (node (ref "U1") (pin "59") (pinfunction "PD12/FSMC_A17/TIM4_CH1/USART3_RTS_59") (pintype "bidirectional"))
    )
    (net (code "71") (name "LCD_DB13") (class "Default")
      (node (ref "U$10") (pin "P14") (pinfunction "DB13_P14") (pintype "bidirectional"))
      (node (ref "U1") (pin "60") (pinfunction "PD13/FSMC_A18/TIM4_CH2_60") (pintype "bidirectional"))
    )
    (net (code "72") (name "LCD_DB14") (class "Default")
      (node (ref "U$10") (pin "P13") (pinfunction "DB14_P13") (pintype "bidirectional"))
      (node (ref "U1") (pin "61") (pinfunction "PD14/FSMC_D0/TIM4_CH3_61") (pintype "bidirectional"))
    )
    (net (code "73") (name "LCD_DB15") (class "Default")
      (node (ref "U$10") (pin "P12") (pinfunction "DB15_P12") (pintype "bidirectional"))
      (node (ref "U1") (pin "62") (pinfunction "PD15/FSMC_D1/TIM4_CH4_62") (pintype "bidirectional"))
    )
    (net (code "74") (name "LCD_RD") (class "Default")
      (node (ref "R9") (pin "1") (pinfunction "1_1") (pintype "passive"))
      (node (ref "U$10") (pin "P28") (pinfunction "RD_P28") (pintype "bidirectional"))
      (node (ref "U1") (pin "3") (pinfunction "PE4/FSMC_A20/DCMI_D4_3") (pintype "bidirectional"))
    )
    (net (code "75") (name "LCD_RESET") (class "Default")
      (node (ref "R11") (pin "1") (pinfunction "1_1") (pintype "passive"))
      (node (ref "U$10") (pin "P11") (pinfunction "RESET_P11") (pintype "bidirectional"))
      (node (ref "U1") (pin "67") (pinfunction "PA8/MCO1/TIM1_CH1/I2C3_SCL_67") (pintype "bidirectional"))
    )
    (net (code "76") (name "LCD_RS") (class "Default")
      (node (ref "R7") (pin "1") (pinfunction "1_1") (pintype "passive"))
      (node (ref "U$10") (pin "P30") (pinfunction "RS_P30") (pintype "bidirectional"))
      (node (ref "U1") (pin "1") (pinfunction "PE2/FSMC_A23/ETH_MII_TXD3_1") (pintype "bidirectional"))
    )
    (net (code "77") (name "LCD_WR") (class "Default")
      (node (ref "R8") (pin "1") (pinfunction "1_1") (pintype "passive"))
      (node (ref "U$10") (pin "P29") (pinfunction "WR_P29") (pintype "bidirectional"))
      (node (ref "U1") (pin "2") (pinfunction "PE3/FSMC_A19_2") (pintype "bidirectional"))
    )
    (net (code "78") (name "LCD_X+") (class "Default")
      (node (ref "U$10") (pin "P38") (pinfunction "X+_P38") (pintype "bidirectional"))
      (node (ref "U1") (pin "36") (pinfunction "PB1/TIM3_CH4/ADC12_IN9_36") (pintype "bidirectional"))
    )
    (net (code "79") (name "LCD_X-") (class "Default")
      (node (ref "U$10") (pin "P36") (pinfunction "X-_P36") (pintype "bidirectional"))
      (node (ref "U1") (pin "51") (pinfunction "PB12/CAN2_RX_51") (pintype "bidirectional"))
    )
    (net (code "80") (name "LCD_Y+") (class "Default")
      (node (ref "U$10") (pin "P37") (pinfunction "Y+_P37") (pintype "bidirectional"))
      (node (ref "U1") (pin "35") (pinfunction "PB0/TIM3_CH3/ADC12_IN8_35") (pintype "bidirectional"))
    )
    (net (code "81") (name "LCD_Y-") (class "Default")
      (node (ref "U$10") (pin "P39") (pinfunction "Y-_P39") (pintype "bidirectional"))
      (node (ref "U1") (pin "54") (pinfunction "PB15/SPI2_MOSI/TIM12_CH2_54") (pintype "bidirectional"))
    )
    (net (code "82") (name "NJTRST") (class "Default")
      (node (ref "U$1") (pin "4") (pinfunction "JTRST_4") (pintype "bidirectional"))
      (node (ref "U1") (pin "90") (pinfunction "PB4/NJTRST/SPI3_MISO/TIMER2_CH2/SPI1_SCK_90") (pintype "bidirectional"))
    )
    (net (code "83") (name "NRST") (class "Default")
      (node (ref "C1") (pin "1") (pinfunction "1_1") (pintype "passive"))
      (node (ref "R1") (pin "1") (pinfunction "1_1") (pintype "passive"))
      (node (ref "SW2") (pin "P$2") (pinfunction "S2_P$2") (pintype "bidirectional"))
      (node (ref "U$1") (pin "7") (pinfunction "NRST_7") (pintype "bidirectional"))
      (node (ref "U1") (pin "14") (pinfunction "NRST_14") (pintype "bidirectional"))
    )
    (net (code "84") (name "Net-(C22-Pad2)") (class "Default")
      (node (ref "C22") (pin "2") (pinfunction "2_2") (pintype "passive"))
      (node (ref "R17") (pin "1") (pinfunction "1_1") (pintype "passive"))
    )
    (net (code "85") (name "Net-(CARD0-PadP1)") (class "Default")
      (node (ref "CARD0") (pin "P1") (pinfunction "P1_P1") (pintype "bidirectional"))
      (node (ref "CARD0") (pin "P2") (pinfunction "P2_P2") (pintype "bidirectional"))
      (node (ref "D1") (pin "C") (pinfunction "C_C") (pintype "passive"))
    )
    (net (code "86") (name "Net-(CARD0-PadP3)") (class "Default")
      (node (ref "CARD0") (pin "P3") (pinfunction "P3_P3") (pintype "bidirectional"))
      (node (ref "D2") (pin "C") (pinfunction "C_C") (pintype "passive"))
    )
    (net (code "87") (name "Net-(CARD0-PadP4)") (class "Default")
      (node (ref "CARD0") (pin "P4") (pinfunction "P4_P4") (pintype "bidirectional"))
      (node (ref "D3") (pin "C") (pinfunction "C_C") (pintype "passive"))
    )
    (net (code "88") (name "Net-(CARD0-PadP6)") (class "Default")
      (node (ref "CARD0") (pin "P6") (pinfunction "P6_P6") (pintype "bidirectional"))
      (node (ref "CARD0") (pin "P7") (pinfunction "P7_P7") (pintype "bidirectional"))
      (node (ref "D11") (pin "A") (pinfunction "A_A") (pintype "passive"))
    )
    (net (code "89") (name "Net-(CARD1-PadP1)") (class "Default")
      (node (ref "CARD1") (pin "P1") (pinfunction "P1_P1") (pintype "bidirectional"))
      (node (ref "CARD1") (pin "P2") (pinfunction "P2_P2") (pintype "bidirectional"))
      (node (ref "D4") (pin "C") (pinfunction "C_C") (pintype "passive"))
    )
    (net (code "90") (name "Net-(CARD1-PadP3)") (class "Default")
      (node (ref "CARD1") (pin "P3") (pinfunction "P3_P3") (pintype "bidirectional"))
      (node (ref "D9") (pin "C") (pinfunction "C_C") (pintype "passive"))
    )
    (net (code "91") (name "Net-(CARD1-PadP4)") (class "Default")
      (node (ref "CARD1") (pin "P4") (pinfunction "P4_P4") (pintype "bidirectional"))
      (node (ref "D10") (pin "C") (pinfunction "C_C") (pintype "passive"))
    )
    (net (code "92") (name "Net-(CARD1-PadP6)") (class "Default")
      (node (ref "CARD1") (pin "P6") (pinfunction "P6_P6") (pintype "bidirectional"))
      (node (ref "CARD1") (pin "P7") (pinfunction "P7_P7") (pintype "bidirectional"))
      (node (ref "D12") (pin "A") (pinfunction "A_A") (pintype "passive"))
    )
    (net (code "93") (name "Net-(D5-PadA)") (class "Default")
      (node (ref "D5") (pin "A") (pinfunction "A_A") (pintype "passive"))
      (node (ref "D8") (pin "C") (pinfunction "C_C") (pintype "passive"))
      (node (ref "F1") (pin "P$2") (pinfunction "P$2_P$2") (pintype "bidirectional"))
    )
    (net (code "94") (name "Net-(D6-PadA)") (class "Default")
      (node (ref "D6") (pin "A") (pinfunction "A_A") (pintype "passive"))
      (node (ref "D7") (pin "C") (pinfunction "C_C") (pintype "passive"))
      (node (ref "U$2") (pin "GND1") (pinfunction "GND1_GND1") (pintype "bidirectional"))
      (node (ref "U$2") (pin "GND2") (pinfunction "GND2_GND2") (pintype "bidirectional"))
      (node (ref "U$2") (pin "P2") (pinfunction "P2_P2") (pintype "bidirectional"))
    )
    (net (code "95") (name "Net-(D13-PadA)") (class "Default")
      (node (ref "D13") (pin "A") (pinfunction "A_A") (pintype "passive"))
      (node (ref "X3") (pin "1") (pinfunction "1_1") (pintype "input"))
    )
    (net (code "96") (name "Net-(F1-PadP$1)") (class "Default")
      (node (ref "F1") (pin "P$1") (pinfunction "P$1_P$1") (pintype "bidirectional"))
      (node (ref "U$2") (pin "P1") (pinfunction "P1_P1") (pintype "bidirectional"))
    )
    (net (code "97") (name "Net-(R13-Pad2)") (class "Default")
      (node (ref "R13") (pin "2") (pinfunction "2_2") (pintype "passive"))
      (node (ref "R14") (pin "2") (pinfunction "2_2") (pintype "passive"))
      (node (ref "U4") (pin "1") (pinfunction "1_1") (pintype "bidirectional"))
    )
    (net (code "98") (name "Net-(U$10-IM0)") (class "Default")
      (node (ref "R10") (pin "2") (pinfunction "2_2") (pintype "passive"))
      (node (ref "U$10") (pin "P10") (pinfunction "IM0_P10") (pintype "bidirectional"))
    )
    (net (code "99") (name "Net-(U$10-LED1)") (class "Default")
      (node (ref "U$10") (pin "P4") (pinfunction "LED4_P4") (pintype "bidirectional"))
      (node (ref "U$10") (pin "P5") (pinfunction "LED3_P5") (pintype "bidirectional"))
      (node (ref "U$10") (pin "P6") (pinfunction "LED2_P6") (pintype "bidirectional"))
      (node (ref "U$10") (pin "P7") (pinfunction "LED1_P7") (pintype "bidirectional"))
      (node (ref "U4") (pin "3") (pinfunction "3_3") (pintype "bidirectional"))
    )
    (net (code "100") (name "Net-(U$10-LEDA)") (class "Default")
      (node (ref "R12") (pin "2") (pinfunction "2_2") (pintype "passive"))
      (node (ref "U$10") (pin "P3") (pinfunction "LEDA_P3") (pintype "bidirectional"))
    )
    (net (code "101") (name "Net-(U1-VCAP_1)") (class "Default")
      (node (ref "C19") (pin "1") (pinfunction "1_1") (pintype "passive"))
      (node (ref "U1") (pin "49") (pinfunction "VCAP_1_49") (pintype "bidirectional"))
    )
    (net (code "102") (name "Net-(U1-VCAP_2)") (class "Default")
      (node (ref "C20") (pin "1") (pinfunction "1_1") (pintype "passive"))
      (node (ref "U1") (pin "73") (pinfunction "VCAP_2_73") (pintype "bidirectional"))
    )
    (net (code "103") (name "Net-(U1-VDDA)") (class "Default")
      (node (ref "L1") (pin "2") (pinfunction "2_2") (pintype "passive"))
      (node (ref "U1") (pin "21") (pinfunction "VREF+_21") (pintype "bidirectional"))
      (node (ref "U1") (pin "22") (pinfunction "VDDA_22") (pintype "bidirectional"))
    )
    (net (code "104") (name "Net-(U3-+IN)") (class "Default")
      (node (ref "C21") (pin "1") (pinfunction "1_1") (pintype "passive"))
      (node (ref "U3") (pin "2") (pinfunction "BYPASS_2") (pintype "bidirectional"))
      (node (ref "U3") (pin "3") (pinfunction "+IN_3") (pintype "bidirectional"))
    )
    (net (code "105") (name "Net-(U3--IN)") (class "Default")
      (node (ref "R17") (pin "2") (pinfunction "2_2") (pintype "passive"))
      (node (ref "U3") (pin "4") (pinfunction "-IN_4") (pintype "bidirectional"))
    )
    (net (code "106") (name "Net-(U3-VO1)") (class "Default")
      (node (ref "U3") (pin "5") (pinfunction "VO1_5") (pintype "bidirectional"))
      (node (ref "U7") (pin "P$2") (pinfunction "P$2_P$2") (pintype "bidirectional"))
    )
    (net (code "107") (name "Net-(U3-VO2)") (class "Default")
      (node (ref "U3") (pin "8") (pinfunction "VO2_8") (pintype "bidirectional"))
      (node (ref "U7") (pin "P$1") (pinfunction "P$1_P$1") (pintype "bidirectional"))
    )
    (net (code "108") (name "Net-(U5-IO1_1)") (class "Default")
      (node (ref "U5") (pin "1") (pinfunction "IO1_1_1") (pintype "bidirectional"))
      (node (ref "X3") (pin "2") (pinfunction "2_2") (pintype "input"))
    )
    (net (code "109") (name "Net-(U5-IO2_1)") (class "Default")
      (node (ref "U5") (pin "3") (pinfunction "IO2_1_3") (pintype "bidirectional"))
      (node (ref "X3") (pin "3") (pinfunction "3_3") (pintype "input"))
    )
    (net (code "110") (name "OSC32_IN") (class "Default")
      (node (ref "C15") (pin "1") (pinfunction "1_1") (pintype "passive"))
      (node (ref "U1") (pin "8") (pinfunction "PC14/OSC32_IN_8") (pintype "bidirectional"))
      (node (ref "X2") (pin "P$2") (pinfunction "XOUT_P$2") (pintype "bidirectional"))
    )
    (net (code "111") (name "OSC32_OUT") (class "Default")
      (node (ref "C14") (pin "1") (pinfunction "1_1") (pintype "passive"))
      (node (ref "U1") (pin "9") (pinfunction "PC15/OSC32_OUT_9") (pintype "bidirectional"))
      (node (ref "X2") (pin "P$1") (pinfunction "XIN_P$1") (pintype "bidirectional"))
    )
    (net (code "112") (name "OSC_IN") (class "Default")
      (node (ref "C17") (pin "1") (pinfunction "1_1") (pintype "passive"))
      (node (ref "U1") (pin "12") (pinfunction "PH0/OSC_IN_12") (pintype "bidirectional"))
      (node (ref "X1") (pin "3") (pinfunction "2_3") (pintype "passive"))
    )
    (net (code "113") (name "OSC_OUT") (class "Default")
      (node (ref "C16") (pin "1") (pinfunction "1_1") (pintype "passive"))
      (node (ref "U1") (pin "13") (pinfunction "PH1/OSC_OUT_13") (pintype "bidirectional"))
      (node (ref "X1") (pin "1") (pinfunction "1_1") (pintype "passive"))
    )
    (net (code "114") (name "PWR_BAT") (class "Default")
      (node (ref "CARD0") (pin "P8") (pinfunction "P8_P8") (pintype "bidirectional"))
      (node (ref "CARD1") (pin "P8") (pinfunction "P8_P8") (pintype "bidirectional"))
      (node (ref "U1") (pin "46") (pinfunction "PE15/FSMC_D12_46") (pintype "bidirectional"))
    )
    (net (code "115") (name "PWR_CHG") (class "Default")
      (node (ref "U$2") (pin "P3") (pinfunction "P3_P3") (pintype "bidirectional"))
      (node (ref "U1") (pin "18") (pinfunction "PC3/SPI2_MOSI/ADC123_IN13_18") (pintype "bidirectional"))
    )
    (net (code "116") (name "USB_DM") (class "Default")
      (node (ref "U1") (pin "70") (pinfunction "PA11/USART1_CTS/CAN1_RX/TIM1_CH4/USB_DM_70") (pintype "bidirectional"))
      (node (ref "U5") (pin "6") (pinfunction "IO1_2_6") (pintype "bidirectional"))
    )
    (net (code "117") (name "USB_DP") (class "Default")
      (node (ref "U1") (pin "71") (pinfunction "PA12/USART1_RTS/CAN1_TX/USB_DP_71") (pintype "bidirectional"))
      (node (ref "U5") (pin "4") (pinfunction "IO2_2_4") (pintype "bidirectional"))
    )
    (net (code "118") (name "VIN") (class "Default")
      (node (ref "D1") (pin "A") (pinfunction "A_A") (pintype "passive"))
      (node (ref "D11") (pin "C") (pinfunction "C_C") (pintype "passive"))
      (node (ref "D12") (pin "C") (pinfunction "C_C") (pintype "passive"))
      (node (ref "D13") (pin "C") (pinfunction "C_C") (pintype "passive"))
      (node (ref "D4") (pin "A") (pinfunction "A_A") (pintype "passive"))
      (node (ref "D5") (pin "C") (pinfunction "C_C") (pintype "passive"))
      (node (ref "D6") (pin "C") (pinfunction "C_C") (pintype "passive"))
      (node (ref "U6") (pin "3") (pinfunction "INPUT_3") (pintype "bidirectional"))
    )
    (net (code "119") (name "unconnected-(U$1-GND1-Pad2)") (class "Default")
      (node (ref "U$1") (pin "2") (pinfunction "GND1_2") (pintype "bidirectional"))
    )
    (net (code "120") (name "unconnected-(U$1-NC-Pad10)") (class "Default")
      (node (ref "U$1") (pin "10") (pinfunction "NC_10") (pintype "bidirectional"))
    )
    (net (code "121") (name "unconnected-(U$7-NC-Pad4)") (class "Default")
      (node (ref "U$7") (pin "4") (pinfunction "NC_4") (pintype "bidirectional"))
    )
    (net (code "122") (name "unconnected-(U$10-FMARK-PadP32)") (class "Default")
      (node (ref "U$10") (pin "P32") (pinfunction "FMARK_P32") (pintype "bidirectional"))
    )
    (net (code "123") (name "unconnected-(U$10-LCD_ID-PadP35)") (class "Default")
      (node (ref "U$10") (pin "P35") (pinfunction "LCD_ID_P35") (pintype "bidirectional"))
    )
    (net (code "124") (name "unconnected-(U$10-NC1-PadP9)") (class "Default")
      (node (ref "U$10") (pin "P9") (pinfunction "NC1_P9") (pintype "bidirectional"))
    )
    (net (code "125") (name "unconnected-(U$10-NC2-PadP1)") (class "Default")
      (node (ref "U$10") (pin "P1") (pinfunction "NC2_P1") (pintype "bidirectional"))
    )
    (net (code "126") (name "unconnected-(U1-PE9{slash}FSMC_D6{slash}TIM1_CH1-Pad40)") (class "Default")
      (node (ref "U1") (pin "40") (pinfunction "PE9/FSMC_D6/TIM1_CH1_40") (pintype "bidirectional"))
    )
    (net (code "127") (name "unconnected-(U1-PE10{slash}FSMC_D7-Pad41)") (class "Default")
      (node (ref "U1") (pin "41") (pinfunction "PE10/FSMC_D7_41") (pintype "bidirectional"))
    )
    (net (code "128") (name "unconnected-(U1-PE11{slash}FSMC_D8{slash}TIM_CH2-Pad42)") (class "Default")
      (node (ref "U1") (pin "42") (pinfunction "PE11/FSMC_D8/TIM_CH2_42") (pintype "bidirectional"))
    )
  )
)
